# Trash.net
KiCad netlist of a schematic drawn in Altium Designer
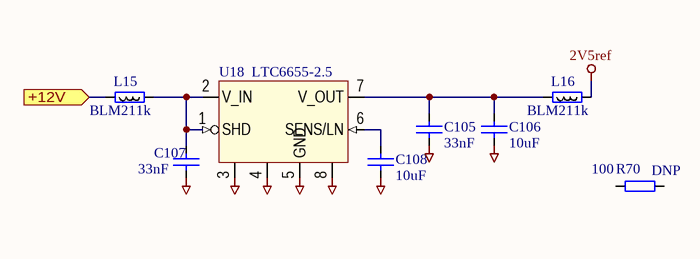
[diagram p0: Trash.SchDoc]

(export (version "E")
  (design (tool "Eeschema 10.0.6"))
  (components
    (comp (ref "C105")
      (value "33nF")
      (footprint "SMD0805CAP")
      (description "Чип конденсатор 0805")
      (fields (field (name "VOLTAGE") "25V") (field (name "TOLERANCE") "20%"))
      (libsource (lib "DDSintLib") (part "C0805"))
    )
    (comp (ref "C106")
      (value "10uF")
      (footprint "SMD0805CAP")
      (description "Чип конденсатор 0805")
      (fields (field (name "VOLTAGE") "25V") (field (name "TOLERANCE") "20%"))
      (libsource (lib "DDSintLib") (part "C0805"))
    )
    (comp (ref "C107")
      (value "33nF")
      (footprint "SMD0805CAP")
      (description "Чип конденсатор 0805")
      (fields (field (name "VOLTAGE") "25V") (field (name "TOLERANCE") "20%"))
      (libsource (lib "DDSintLib") (part "C0805"))
    )
    (comp (ref "C108")
      (value "10uF")
      (footprint "SMD0805CAP")
      (description "Чип конденсатор 0805")
      (fields (field (name "VOLTAGE") "25V") (field (name "TOLERANCE") "20%"))
      (libsource (lib "DDSintLib") (part "C0805"))
    )
    (comp (ref "L15")
      (value "BLM211k")
      (footprint "RESC2012X50N")
      (description "SMD Ferrite bead 0805")
      (libsource (lib "DDSintLib") (part "BLM21"))
    )
    (comp (ref "L16")
      (value "BLM211k")
      (footprint "RESC2012X50N")
      (description "SMD Ferrite bead 0805")
      (libsource (lib "DDSintLib") (part "BLM21"))
    )
    (comp (ref "R70")
      (value "100")
      (footprint "SMD0805RES")
      (description "Чип резистор 0805")
      (fields (field (name "SOLDER OPTION") "DNP") (field (name "TOLERANCE") "1%"))
      (libsource (lib "DDSintLib") (part "R0805"))
    )
    (comp (ref "U18")
      (value "LTC6655-2.5")
      (footprint "DDS1:SOP65P488X110-8N")
      (description "Low noise precision reference,")
      (fields (field (name "VOLTAGE") "max13.2V"))
      (libsource (lib "DDS1") (part "LTC6655B-5"))
    )
  )
  (nets
    (net (code "1") (name "/+12V") (class "Default")
      (node (ref "L15") (pin "1") (pinfunction "1_1") (pintype "passive"))
    )
    (net (code "2") (name "2V5ref") (class "Default")
      (node (ref "L16") (pin "2") (pinfunction "2_2") (pintype "passive"))
    )
    (net (code "3") (name "GND") (class "Default")
      (node (ref "C105") (pin "2") (pinfunction "2_2") (pintype "passive"))
      (node (ref "C106") (pin "1") (pinfunction "1_1") (pintype "passive"))
      (node (ref "C107") (pin "1") (pinfunction "1_1") (pintype "passive"))
      (node (ref "C108") (pin "1") (pinfunction "1_1") (pintype "passive"))
      (node (ref "U18") (pin "3") (pinfunction "GND_3") (pintype "passive"))
      (node (ref "U18") (pin "4") (pinfunction "GND_4") (pintype "passive"))
      (node (ref "U18") (pin "5") (pinfunction "GND_5") (pintype "passive"))
      (node (ref "U18") (pin "8") (pinfunction "GND_8") (pintype "power_in"))
    )
    (net (code "4") (name "Net-(U18-SENS{slash}LN)") (class "Default")
      (node (ref "C108") (pin "2") (pinfunction "2_2") (pintype "passive"))
      (node (ref "U18") (pin "6") (pinfunction "SENS/LN_6") (pintype "input"))
    )
    (net (code "5") (name "Net-(U18-SHD)") (class "Default")
      (node (ref "C107") (pin "2") (pinfunction "2_2") (pintype "passive"))
      (node (ref "L15") (pin "2") (pinfunction "2_2") (pintype "passive"))
      (node (ref "U18") (pin "1") (pinfunction "SHD_1") (pintype "input"))
      (node (ref "U18") (pin "2") (pinfunction "V_IN_2") (pintype "power_in"))
    )
    (net (code "6") (name "Net-(U18-V_OUT)") (class "Default")
      (node (ref "C105") (pin "1") (pinfunction "1_1") (pintype "passive"))
      (node (ref "C106") (pin "2") (pinfunction "2_2") (pintype "passive"))
      (node (ref "L16") (pin "1") (pinfunction "1_1") (pintype "passive"))
      (node (ref "U18") (pin "7") (pinfunction "V_OUT_7") (pintype "passive"))
    )
    (net (code "7") (name "unconnected-(R70-Pad1)") (class "Default")
      (node (ref "R70") (pin "1") (pinfunction "1_1") (pintype "passive"))
    )
    (net (code "8") (name "unconnected-(R70-Pad2)") (class "Default")
      (node (ref "R70") (pin "2") (pinfunction "2_2") (pintype "passive"))
    )
  )
)
